# smd.net
KiCad netlist of a schematic drawn in EAGLE
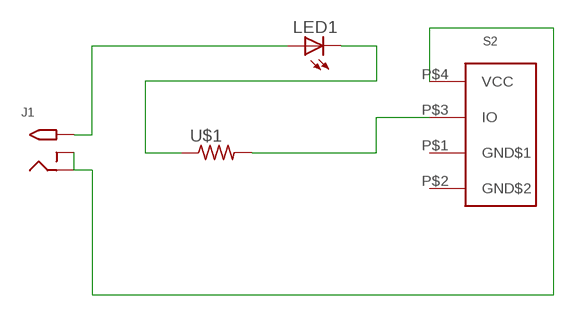
[diagram p0: schematic, sheet 1]

(export (version "E")
  (design (tool "Eeschema 10.0.6"))
  (components
    (comp (ref "J1")
      (value "2.1MMJACKTHM")
      (footprint "eagle-import:PJ-102A")
      (libsource (lib "eagle-import") (part "2.1MMJACKTHM"))
    )
    (comp (ref "LED1")
      (value "LED5MM")
      (footprint "eagle-import:LED5MM")
      (libsource (lib "eagle-import") (part "LED5MM"))
    )
    (comp (ref "S2")
      (value "BUTTON-TACTILE-SQUARE")
      (footprint "eagle-import:BUTTON-TACTILE-SQUARE")
      (libsource (lib "eagle-import") (part "BUTTON-TACTILE-SQUARE"))
    )
    (comp (ref "U$1")
      (value "RESISTORTH-1/4W-CARBON")
      (footprint "eagle-import:RESAD1160W55L680D260_HS")
      (libsource (lib "eagle-import") (part "RESISTORTH-1/4W-CARBON"))
    )
  )
  (nets
    (net (code "1") (name "/GND$1") (class "Default")
      (node (ref "S2") (pin "P$1") (pinfunction "GND$1_P$1") (pintype "power_in"))
    )
    (net (code "2") (name "/GND$2") (class "Default")
      (node (ref "S2") (pin "P$2") (pinfunction "GND$2_P$2") (pintype "power_in"))
    )
    (net (code "3") (name "Net-(J1-PadTIP)") (class "Default")
      (node (ref "J1") (pin "TIP") (pinfunction "TIP_TIP") (pintype "bidirectional"))
      (node (ref "LED1") (pin "A") (pinfunction "A_A") (pintype "passive"))
    )
    (net (code "4") (name "Net-(LED1-C)") (class "Default")
      (node (ref "LED1") (pin "K") (pinfunction "C_K") (pintype "passive"))
      (node (ref "U$1") (pin "1") (pinfunction "1_1") (pintype "passive"))
    )
    (net (code "5") (name "Net-(S2-IO)") (class "Default")
      (node (ref "S2") (pin "P$3") (pinfunction "IO_P$3") (pintype "bidirectional"))
      (node (ref "U$1") (pin "2") (pinfunction "2_2") (pintype "passive"))
    )
    (net (code "6") (name "Net-(S2-VCC)") (class "Default")
      (node (ref "J1") (pin "RING") (pinfunction "RING_RING") (pintype "bidirectional"))
      (node (ref "J1") (pin "RING_SW") (pinfunction "RING_SW_RING_SW") (pintype "bidirectional"))
      (node (ref "S2") (pin "P$4") (pinfunction "VCC_P$4") (pintype "power_in"))
    )
  )
)
